# Proto_shield_REV3.net
KiCad netlist of a schematic drawn in EAGLE
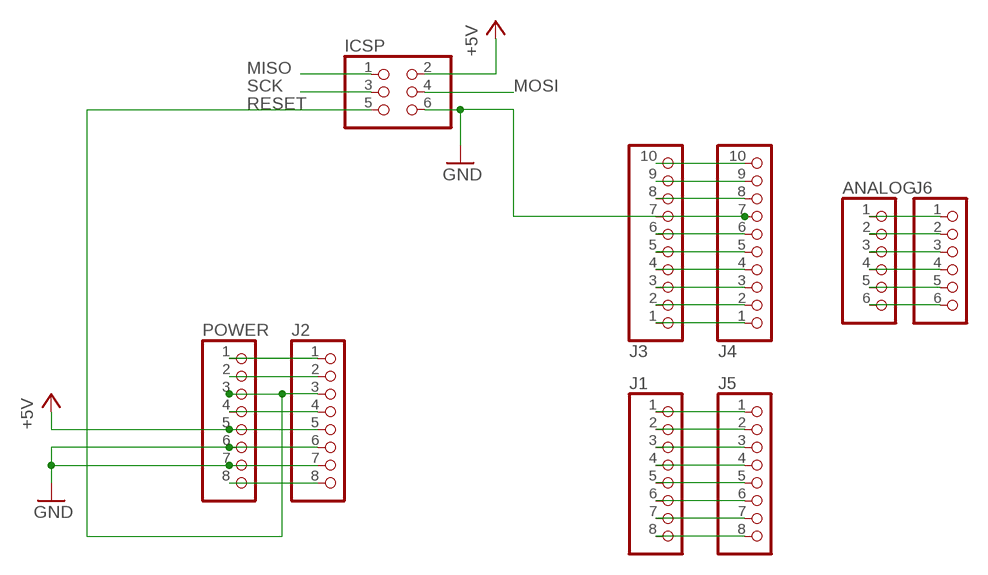
[diagram p0: schematic, sheet 1]

(export (version "E")
  (design (tool "Eeschema 10.0.6"))
  (components
    (comp (ref "ANALOG")
      (value "PINHD-1X6")
      (footprint "eagle-import:1X06")
      (libsource (lib "eagle-import") (part "PINHD-1X6"))
    )
    (comp (ref "ICSP")
      (value "PINHD-2X3")
      (footprint "eagle-import:2X03")
      (libsource (lib "eagle-import") (part "PINHD-2X3"))
    )
    (comp (ref "J1")
      (value "PINHD-1X8TH")
      (footprint "eagle-import:1X08-TH")
      (libsource (lib "eagle-import") (part "PINHD-1X8TH"))
    )
    (comp (ref "J2")
      (value "PINHD-1X8TH")
      (footprint "eagle-import:1X08-TH")
      (libsource (lib "eagle-import") (part "PINHD-1X8TH"))
    )
    (comp (ref "J3")
      (value "PINHD-1X10TH")
      (footprint "eagle-import:1X10-TH")
      (libsource (lib "eagle-import") (part "PINHD-1X10TH"))
    )
    (comp (ref "J4")
      (value "PINHD-1X10TH")
      (footprint "eagle-import:1X10-TH")
      (libsource (lib "eagle-import") (part "PINHD-1X10TH"))
    )
    (comp (ref "J5")
      (value "PINHD-1X8TH")
      (footprint "eagle-import:1X08-TH")
      (libsource (lib "eagle-import") (part "PINHD-1X8TH"))
    )
    (comp (ref "J6")
      (value "PINHD-1X6")
      (footprint "eagle-import:1X06")
      (libsource (lib "eagle-import") (part "PINHD-1X6"))
    )
    (comp (ref "POWER")
      (value "PINHD-1X8TH")
      (footprint "eagle-import:1X08-TH")
      (libsource (lib "eagle-import") (part "PINHD-1X8TH"))
    )
  )
  (nets
    (net (code "1") (name "+5V") (class "Default")
      (node (ref "ICSP") (pin "2") (pinfunction "2_2") (pintype "passive"))
      (node (ref "J2") (pin "5") (pinfunction "5_5") (pintype "passive"))
      (node (ref "POWER") (pin "5") (pinfunction "5_5") (pintype "passive"))
    )
    (net (code "2") (name "/MISO") (class "Default")
      (node (ref "ICSP") (pin "1") (pinfunction "1_1") (pintype "passive"))
    )
    (net (code "3") (name "/MOSI") (class "Default")
      (node (ref "ICSP") (pin "4") (pinfunction "4_4") (pintype "passive"))
    )
    (net (code "4") (name "/RESET") (class "Default")
      (node (ref "ICSP") (pin "5") (pinfunction "5_5") (pintype "passive"))
      (node (ref "J2") (pin "3") (pinfunction "3_3") (pintype "passive"))
      (node (ref "POWER") (pin "3") (pinfunction "3_3") (pintype "passive"))
    )
    (net (code "5") (name "/SCK") (class "Default")
      (node (ref "ICSP") (pin "3") (pinfunction "3_3") (pintype "passive"))
    )
    (net (code "6") (name "GND") (class "Default")
      (node (ref "ICSP") (pin "6") (pinfunction "6_6") (pintype "passive"))
      (node (ref "J2") (pin "7") (pinfunction "7_7") (pintype "passive"))
      (node (ref "J3") (pin "7") (pinfunction "7_7") (pintype "passive"))
      (node (ref "J4") (pin "7") (pinfunction "7_7") (pintype "passive"))
      (node (ref "POWER") (pin "7") (pinfunction "7_7") (pintype "passive"))
    )
    (net (code "7") (name "Net-(ANALOG-Pad1)") (class "Default")
      (node (ref "ANALOG") (pin "1") (pinfunction "1_1") (pintype "passive"))
      (node (ref "J6") (pin "1") (pinfunction "1_1") (pintype "passive"))
    )
    (net (code "8") (name "Net-(ANALOG-Pad2)") (class "Default")
      (node (ref "ANALOG") (pin "2") (pinfunction "2_2") (pintype "passive"))
      (node (ref "J6") (pin "2") (pinfunction "2_2") (pintype "passive"))
    )
    (net (code "9") (name "Net-(ANALOG-Pad3)") (class "Default")
      (node (ref "ANALOG") (pin "3") (pinfunction "3_3") (pintype "passive"))
      (node (ref "J6") (pin "3") (pinfunction "3_3") (pintype "passive"))
    )
    (net (code "10") (name "Net-(ANALOG-Pad4)") (class "Default")
      (node (ref "ANALOG") (pin "4") (pinfunction "4_4") (pintype "passive"))
      (node (ref "J6") (pin "4") (pinfunction "4_4") (pintype "passive"))
    )
    (net (code "11") (name "Net-(ANALOG-Pad5)") (class "Default")
      (node (ref "ANALOG") (pin "5") (pinfunction "5_5") (pintype "passive"))
      (node (ref "J6") (pin "5") (pinfunction "5_5") (pintype "passive"))
    )
    (net (code "12") (name "Net-(ANALOG-Pad6)") (class "Default")
      (node (ref "ANALOG") (pin "6") (pinfunction "6_6") (pintype "passive"))
      (node (ref "J6") (pin "6") (pinfunction "6_6") (pintype "passive"))
    )
    (net (code "13") (name "Net-(J1-Pad1)") (class "Default")
      (node (ref "J1") (pin "1") (pinfunction "1_1") (pintype "passive"))
      (node (ref "J5") (pin "1") (pinfunction "1_1") (pintype "passive"))
    )
    (net (code "14") (name "Net-(J1-Pad2)") (class "Default")
      (node (ref "J1") (pin "2") (pinfunction "2_2") (pintype "passive"))
      (node (ref "J5") (pin "2") (pinfunction "2_2") (pintype "passive"))
    )
    (net (code "15") (name "Net-(J1-Pad3)") (class "Default")
      (node (ref "J1") (pin "3") (pinfunction "3_3") (pintype "passive"))
      (node (ref "J5") (pin "3") (pinfunction "3_3") (pintype "passive"))
    )
    (net (code "16") (name "Net-(J1-Pad4)") (class "Default")
      (node (ref "J1") (pin "4") (pinfunction "4_4") (pintype "passive"))
      (node (ref "J5") (pin "4") (pinfunction "4_4") (pintype "passive"))
    )
    (net (code "17") (name "Net-(J1-Pad5)") (class "Default")
      (node (ref "J1") (pin "5") (pinfunction "5_5") (pintype "passive"))
      (node (ref "J5") (pin "5") (pinfunction "5_5") (pintype "passive"))
    )
    (net (code "18") (name "Net-(J1-Pad6)") (class "Default")
      (node (ref "J1") (pin "6") (pinfunction "6_6") (pintype "passive"))
      (node (ref "J5") (pin "6") (pinfunction "6_6") (pintype "passive"))
    )
    (net (code "19") (name "Net-(J1-Pad7)") (class "Default")
      (node (ref "J1") (pin "7") (pinfunction "7_7") (pintype "passive"))
      (node (ref "J5") (pin "7") (pinfunction "7_7") (pintype "passive"))
    )
    (net (code "20") (name "Net-(J1-Pad8)") (class "Default")
      (node (ref "J1") (pin "8") (pinfunction "8_8") (pintype "passive"))
      (node (ref "J5") (pin "8") (pinfunction "8_8") (pintype "passive"))
    )
    (net (code "21") (name "Net-(J2-Pad1)") (class "Default")
      (node (ref "J2") (pin "1") (pinfunction "1_1") (pintype "passive"))
      (node (ref "POWER") (pin "1") (pinfunction "1_1") (pintype "passive"))
    )
    (net (code "22") (name "Net-(J2-Pad2)") (class "Default")
      (node (ref "J2") (pin "2") (pinfunction "2_2") (pintype "passive"))
      (node (ref "POWER") (pin "2") (pinfunction "2_2") (pintype "passive"))
    )
    (net (code "23") (name "Net-(J2-Pad4)") (class "Default")
      (node (ref "J2") (pin "4") (pinfunction "4_4") (pintype "passive"))
      (node (ref "POWER") (pin "4") (pinfunction "4_4") (pintype "passive"))
    )
    (net (code "24") (name "Net-(J2-Pad6)") (class "Default")
      (node (ref "J2") (pin "6") (pinfunction "6_6") (pintype "passive"))
      (node (ref "POWER") (pin "6") (pinfunction "6_6") (pintype "passive"))
    )
    (net (code "25") (name "Net-(J2-Pad8)") (class "Default")
      (node (ref "J2") (pin "8") (pinfunction "8_8") (pintype "passive"))
      (node (ref "POWER") (pin "8") (pinfunction "8_8") (pintype "passive"))
    )
    (net (code "26") (name "Net-(J3-Pad1)") (class "Default")
      (node (ref "J3") (pin "1") (pinfunction "1_1") (pintype "passive"))
      (node (ref "J4") (pin "1") (pinfunction "1_1") (pintype "passive"))
    )
    (net (code "27") (name "Net-(J3-Pad2)") (class "Default")
      (node (ref "J3") (pin "2") (pinfunction "2_2") (pintype "passive"))
      (node (ref "J4") (pin "2") (pinfunction "2_2") (pintype "passive"))
    )
    (net (code "28") (name "Net-(J3-Pad3)") (class "Default")
      (node (ref "J3") (pin "3") (pinfunction "3_3") (pintype "passive"))
      (node (ref "J4") (pin "3") (pinfunction "3_3") (pintype "passive"))
    )
    (net (code "29") (name "Net-(J3-Pad4)") (class "Default")
      (node (ref "J3") (pin "4") (pinfunction "4_4") (pintype "passive"))
      (node (ref "J4") (pin "4") (pinfunction "4_4") (pintype "passive"))
    )
    (net (code "30") (name "Net-(J3-Pad5)") (class "Default")
      (node (ref "J3") (pin "5") (pinfunction "5_5") (pintype "passive"))
      (node (ref "J4") (pin "5") (pinfunction "5_5") (pintype "passive"))
    )
    (net (code "31") (name "Net-(J3-Pad6)") (class "Default")
      (node (ref "J3") (pin "6") (pinfunction "6_6") (pintype "passive"))
      (node (ref "J4") (pin "6") (pinfunction "6_6") (pintype "passive"))
    )
    (net (code "32") (name "Net-(J3-Pad8)") (class "Default")
      (node (ref "J3") (pin "8") (pinfunction "8_8") (pintype "passive"))
      (node (ref "J4") (pin "8") (pinfunction "8_8") (pintype "passive"))
    )
    (net (code "33") (name "Net-(J3-Pad9)") (class "Default")
      (node (ref "J3") (pin "9") (pinfunction "9_9") (pintype "passive"))
      (node (ref "J4") (pin "9") (pinfunction "9_9") (pintype "passive"))
    )
    (net (code "34") (name "Net-(J3-Pad10)") (class "Default")
      (node (ref "J3") (pin "10") (pinfunction "10_10") (pintype "passive"))
      (node (ref "J4") (pin "10") (pinfunction "10_10") (pintype "passive"))
    )
  )
)
